# level_shifter_sch.net
KiCad netlist of a schematic drawn in Altium Designer
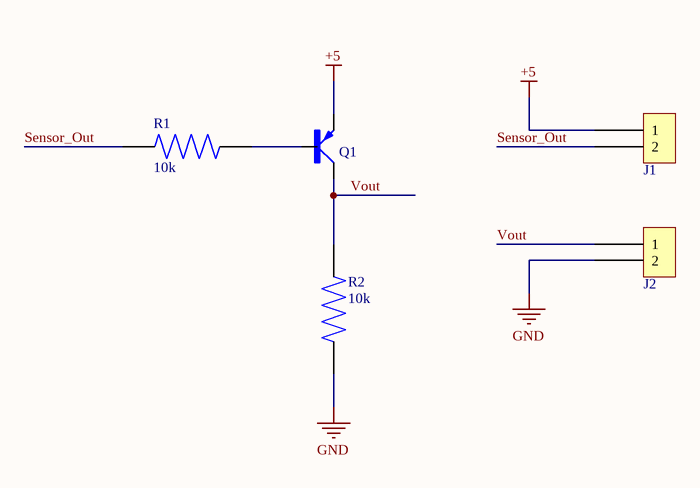
[diagram p0: level_shifter_sch.SchDoc]

(export (version "E")
  (design (tool "Eeschema 10.0.6"))
  (components
    (comp (ref "J1")
      (value "Terminal Block 1x2")
      (footprint "TERMINAL BLOCK 1X2")
      (description "Fixed Terminal Block , screw type, 5.08 , horizontal, 2 poles, CUI Blue, slotted screw, PCB mount")
      (libsource (lib "level_shifter_schLib") (part "Terminal Block 1x2"))
    )
    (comp (ref "J2")
      (value "Terminal Block 1x2")
      (footprint "TERMINAL BLOCK 1X2")
      (description "Fixed Terminal Block , screw type, 5.08 , horizontal, 2 poles, CUI Blue, slotted screw, PCB mount")
      (libsource (lib "level_shifter_schLib") (part "Terminal Block 1x2"))
    )
    (comp (ref "Q1")
      (value "BC327")
      (footprint "TO-92-3")
      (description "Bipolar (BJT) Transistor PNP 45V 800mA 100MHz 625mW Through Hole TO-92-3")
      (libsource (lib "level_shifter_schLib") (part "BC327"))
    )
    (comp (ref "R1")
      (value "10k")
      (footprint "THT RESISTOR")
      (description "Carbon Film Resistor Through Hole 10k")
      (fields (field (name "Comment") "Resistor 10k"))
      (libsource (lib "level_shifter_schLib") (part "Resistor 10k"))
    )
    (comp (ref "R2")
      (value "10k")
      (footprint "THT RESISTOR")
      (description "Carbon Film Resistor Through Hole 10k")
      (fields (field (name "Comment") "Resistor 10k"))
      (libsource (lib "level_shifter_schLib") (part "Resistor 10k"))
    )
  )
  (nets
    (net (code "1") (name "+5") (class "Default")
      (node (ref "J1") (pin "1") (pinfunction "1_1") (pintype "passive"))
      (node (ref "Q1") (pin "E") (pinfunction "E_E") (pintype "passive"))
    )
    (net (code "2") (name "/Sensor_Out") (class "Default")
      (node (ref "J1") (pin "2") (pinfunction "2_2") (pintype "passive"))
      (node (ref "R1") (pin "1") (pinfunction "1_1") (pintype "passive"))
    )
    (net (code "3") (name "/Vout") (class "Default")
      (node (ref "J2") (pin "1") (pinfunction "1_1") (pintype "passive"))
      (node (ref "Q1") (pin "C") (pinfunction "C_C") (pintype "passive"))
      (node (ref "R2") (pin "2") (pinfunction "2_2") (pintype "passive"))
    )
    (net (code "4") (name "GND") (class "Default")
      (node (ref "J2") (pin "2") (pinfunction "2_2") (pintype "passive"))
      (node (ref "R2") (pin "1") (pinfunction "1_1") (pintype "passive"))
    )
    (net (code "5") (name "Net-(Q1-PadB)") (class "Default")
      (node (ref "Q1") (pin "B") (pinfunction "B_B") (pintype "passive"))
      (node (ref "R1") (pin "2") (pinfunction "2_2") (pintype "passive"))
    )
  )
)
